# MY_AVR.net
KiCad netlist of a schematic drawn in Altium Designer
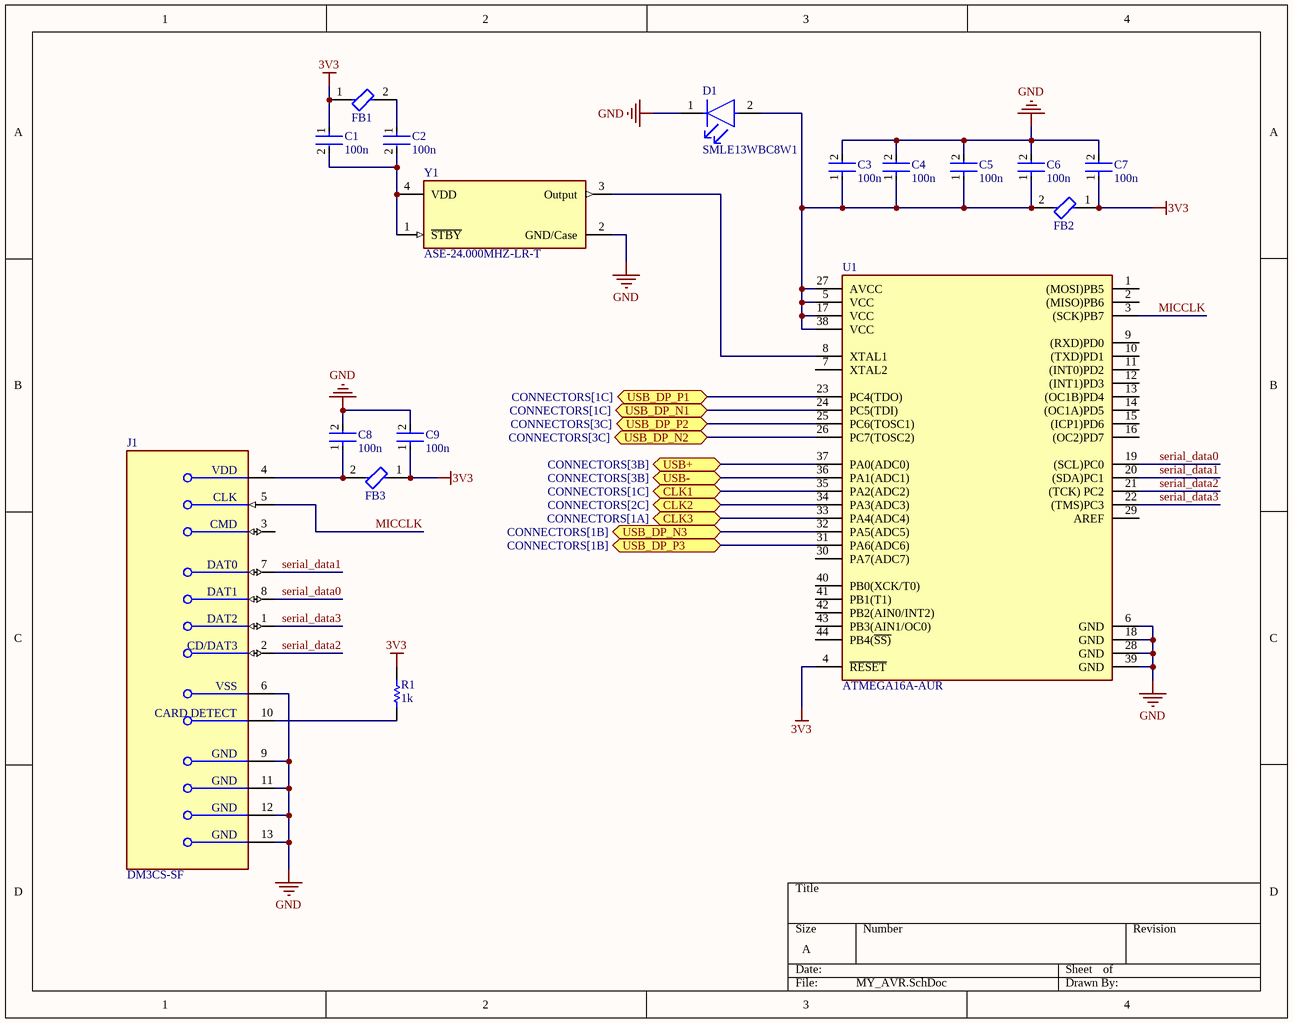
[diagram p0: MY_AVR.SchDoc]

(export (version "E")
  (design (tool "Eeschema 10.0.6"))
  (components
    (comp (ref "C1")
      (value "100n")
      (footprint "FP-CL10-IPC_C")
      (description "Cap Ceramic 4.7uF 10V X5R ±10% Pad SMD 0603 +85°C T/R")
      (fields (field (name "TOLERANCE") "10%"))
      (libsource (lib "Altium Content Vault") (part "b4654b650e69147ec39a6b967a45e02"))
    )
    (comp (ref "C2")
      (value "100n")
      (footprint "FP-CL10-IPC_C")
      (description "Cap Ceramic 4.7uF 10V X5R ±10% Pad SMD 0603 +85°C T/R")
      (fields (field (name "TOLERANCE") "10%"))
      (libsource (lib "Altium Content Vault") (part "b4654b650e69147ec39a6b967a45e02"))
    )
    (comp (ref "C3")
      (value "100n")
      (footprint "FP-CL10-IPC_C")
      (description "Cap Ceramic 4.7uF 10V X5R ±10% Pad SMD 0603 +85°C T/R")
      (fields (field (name "TOLERANCE") "10%"))
      (libsource (lib "Altium Content Vault") (part "b4654b650e69147ec39a6b967a45e02"))
    )
    (comp (ref "C4")
      (value "100n")
      (footprint "FP-CL10-IPC_C")
      (description "Cap Ceramic 4.7uF 10V X5R ±10% Pad SMD 0603 +85°C T/R")
      (fields (field (name "TOLERANCE") "10%"))
      (libsource (lib "Altium Content Vault") (part "b4654b650e69147ec39a6b967a45e02"))
    )
    (comp (ref "C5")
      (value "100n")
      (footprint "FP-CL10-IPC_C")
      (description "Cap Ceramic 4.7uF 10V X5R ±10% Pad SMD 0603 +85°C T/R")
      (fields (field (name "TOLERANCE") "10%"))
      (libsource (lib "Altium Content Vault") (part "b4654b650e69147ec39a6b967a45e02"))
    )
    (comp (ref "C6")
      (value "100n")
      (footprint "FP-CL10-IPC_C")
      (description "Cap Ceramic 4.7uF 10V X5R ±10% Pad SMD 0603 +85°C T/R")
      (fields (field (name "TOLERANCE") "10%"))
      (libsource (lib "Altium Content Vault") (part "b4654b650e69147ec39a6b967a45e02"))
    )
    (comp (ref "C7")
      (value "100n")
      (footprint "FP-CL10-IPC_C")
      (description "Cap Ceramic 4.7uF 10V X5R ±10% Pad SMD 0603 +85°C T/R")
      (fields (field (name "TOLERANCE") "10%"))
      (libsource (lib "Altium Content Vault") (part "b4654b650e69147ec39a6b967a45e02"))
    )
    (comp (ref "C8")
      (value "100n")
      (footprint "FP-CL10-IPC_C")
      (description "Cap Ceramic 4.7uF 10V X5R ±10% Pad SMD 0603 +85°C T/R")
      (fields (field (name "TOLERANCE") "10%"))
      (libsource (lib "Altium Content Vault") (part "b4654b650e69147ec39a6b967a45e02"))
    )
    (comp (ref "C9")
      (value "100n")
      (footprint "FP-CL10-IPC_C")
      (description "Cap Ceramic 4.7uF 10V X5R ±10% Pad SMD 0603 +85°C T/R")
      (fields (field (name "TOLERANCE") "10%"))
      (libsource (lib "Altium Content Vault") (part "b4654b650e69147ec39a6b967a45e02"))
    )
    (comp (ref "D1")
      (value "SMLE13WBC8W1")
      (footprint "FP-SMLE13WBC8W1-MFG")
      (description "LED WHITE 0603 SMD")
      (fields
        (field (name "OCTOPART") "https://octopart.com/smle13wbc8w1-rohm-22224565")
        (field (name "MANUFACTURER") "Rohm")
      )
      (libsource (lib "Altium Content Vault") (part "8706943c75ba83719d021d2fdc84c58"))
    )
    (comp (ref "FB1")
      (value "BLM18KG121TN1D")
      (footprint "FP-BLM18-0_15-t0_6-d1_2-IPC_A")
      (description "FERRITE BEAD 120 OHM 0603 1LN")
      (fields (field (name "TOLERANCE") "25%"))
      (libsource (lib "Altium Content Vault") (part "5f30dd21d616792df468990f7003faa"))
    )
    (comp (ref "FB2")
      (value "BLM18KG121TN1D")
      (footprint "FP-BLM18-0_15-t0_6-d1_2-IPC_A")
      (description "FERRITE BEAD 120 OHM 0603 1LN")
      (fields (field (name "TOLERANCE") "25%"))
      (libsource (lib "Altium Content Vault") (part "5f30dd21d616792df468990f7003faa"))
    )
    (comp (ref "FB3")
      (value "BLM18KG121TN1D")
      (footprint "FP-BLM18-0_15-t0_6-d1_2-IPC_A")
      (description "FERRITE BEAD 120 OHM 0603 1LN")
      (fields (field (name "TOLERANCE") "25%"))
      (libsource (lib "Altium Content Vault") (part "5f30dd21d616792df468990f7003faa"))
    )
    (comp (ref "J1")
      (value "DM3CS-SF")
      (footprint "FP-DM3CS-SF-MFG")
      (description "CONN MICRO SD CARD HINGED TYPE")
      (libsource (lib "Altium Content Vault") (part "bac915de5305cfdd1ca301aae530106"))
    )
    (comp (ref "R1")
      (value "1k")
      (footprint "RESC2013X60X35ML10T20")
      (fields (field (name "TOLERANCE") "5%") (field (name "MANUFACTURER") "Yageo"))
      (libsource (lib "Altium Content Vault") (part "RES-2"))
    )
    (comp (ref "U1")
      (value "ATMEGA16A-AUR")
      (footprint "FP-44A-MFG")
      (description "IC MCU 8BIT 16KB FLASH 44TQFP")
      (libsource (lib "Altium Content Vault") (part "ed42ffdc3273df72733ccc2dd2ee123"))
    )
    (comp (ref "Y1")
      (value "ASE-24.000MHZ-LR-T")
      (footprint "FP-ASE-MFG")
      (description "XTAL Oscillator 24MHz ±25ppm CMOS 3.3V 4-SMD 3.2mm x 2.5mm")
      (libsource (lib "Altium Content Vault") (part "61a724e6190563596ac712fef61ad37"))
    )
  )
  (nets
    (net (code "1") (name "/CLK1") (class "Default")
      (node (ref "U1") (pin "35") (pinfunction "PA2(ADC2)_35") (pintype "passive"))
    )
    (net (code "2") (name "/CLK2") (class "Default")
      (node (ref "U1") (pin "34") (pinfunction "PA3(ADC3)_34") (pintype "passive"))
    )
    (net (code "3") (name "/CLK3") (class "Default")
      (node (ref "U1") (pin "33") (pinfunction "PA4(ADC4)_33") (pintype "passive"))
    )
    (net (code "4") (name "/MICCLK") (class "Default")
      (node (ref "J1") (pin "5") (pinfunction "CLK_5") (pintype "input"))
      (node (ref "U1") (pin "3") (pinfunction "(SCK)PB7_3") (pintype "passive"))
    )
    (net (code "5") (name "/USB+") (class "Default")
      (node (ref "U1") (pin "37") (pinfunction "PA0(ADC0)_37") (pintype "passive"))
    )
    (net (code "6") (name "/USB-") (class "Default")
      (node (ref "U1") (pin "36") (pinfunction "PA1(ADC1)_36") (pintype "passive"))
    )
    (net (code "7") (name "/USB_DP_N1") (class "Default")
      (node (ref "U1") (pin "24") (pinfunction "PC5(TDI)_24") (pintype "passive"))
    )
    (net (code "8") (name "/USB_DP_N2") (class "Default")
      (node (ref "U1") (pin "26") (pinfunction "PC7(TOSC2)_26") (pintype "passive"))
    )
    (net (code "9") (name "/USB_DP_N3") (class "Default")
      (node (ref "U1") (pin "32") (pinfunction "PA5(ADC5)_32") (pintype "passive"))
    )
    (net (code "10") (name "/USB_DP_P1") (class "Default")
      (node (ref "U1") (pin "23") (pinfunction "PC4(TDO)_23") (pintype "passive"))
    )
    (net (code "11") (name "/USB_DP_P2") (class "Default")
      (node (ref "U1") (pin "25") (pinfunction "PC6(TOSC1)_25") (pintype "passive"))
    )
    (net (code "12") (name "/USB_DP_P3") (class "Default")
      (node (ref "U1") (pin "31") (pinfunction "PA6(ADC6)_31") (pintype "passive"))
    )
    (net (code "13") (name "/serial_data0") (class "Default")
      (node (ref "J1") (pin "8") (pinfunction "DAT1_8") (pintype "bidirectional"))
      (node (ref "U1") (pin "19") (pinfunction "(SCL)PC0_19") (pintype "passive"))
    )
    (net (code "14") (name "/serial_data1") (class "Default")
      (node (ref "J1") (pin "7") (pinfunction "DAT0_7") (pintype "bidirectional"))
      (node (ref "U1") (pin "20") (pinfunction "(SDA)PC1_20") (pintype "passive"))
    )
    (net (code "15") (name "/serial_data2") (class "Default")
      (node (ref "J1") (pin "2") (pinfunction "CD/DAT3_2") (pintype "bidirectional"))
      (node (ref "U1") (pin "21") (pinfunction "(TCK)_PC2_21") (pintype "passive"))
    )
    (net (code "16") (name "/serial_data3") (class "Default")
      (node (ref "J1") (pin "1") (pinfunction "DAT2_1") (pintype "bidirectional"))
      (node (ref "U1") (pin "22") (pinfunction "(TMS)PC3_22") (pintype "passive"))
    )
    (net (code "17") (name "3V3") (class "Default")
      (node (ref "C1") (pin "1") (pinfunction "1_1") (pintype "passive"))
      (node (ref "C7") (pin "1") (pinfunction "1_1") (pintype "passive"))
      (node (ref "C9") (pin "1") (pinfunction "1_1") (pintype "passive"))
      (node (ref "FB1") (pin "1") (pinfunction "1_1") (pintype "passive"))
      (node (ref "FB2") (pin "1") (pinfunction "1_1") (pintype "passive"))
      (node (ref "FB3") (pin "1") (pinfunction "1_1") (pintype "passive"))
      (node (ref "R1") (pin "1") (pinfunction "1_1") (pintype "passive"))
      (node (ref "U1") (pin "4") (pinfunction "~{RESET}_4") (pintype "passive"))
    )
    (net (code "18") (name "GND") (class "Default")
      (node (ref "C3") (pin "2") (pinfunction "2_2") (pintype "passive"))
      (node (ref "C4") (pin "2") (pinfunction "2_2") (pintype "passive"))
      (node (ref "C5") (pin "2") (pinfunction "2_2") (pintype "passive"))
      (node (ref "C6") (pin "2") (pinfunction "2_2") (pintype "passive"))
      (node (ref "C7") (pin "2") (pinfunction "2_2") (pintype "passive"))
      (node (ref "C8") (pin "2") (pinfunction "2_2") (pintype "passive"))
      (node (ref "C9") (pin "2") (pinfunction "2_2") (pintype "passive"))
      (node (ref "D1") (pin "1") (pinfunction "C_1") (pintype "passive"))
      (node (ref "J1") (pin "11") (pinfunction "GND_11") (pintype "power_in"))
      (node (ref "J1") (pin "12") (pinfunction "GND_12") (pintype "power_in"))
      (node (ref "J1") (pin "13") (pinfunction "GND_13") (pintype "power_in"))
      (node (ref "J1") (pin "6") (pinfunction "VSS_6") (pintype "power_in"))
      (node (ref "J1") (pin "9") (pinfunction "GND_9") (pintype "power_in"))
      (node (ref "U1") (pin "18") (pinfunction "GND_18") (pintype "passive"))
      (node (ref "U1") (pin "28") (pinfunction "GND_28") (pintype "passive"))
      (node (ref "U1") (pin "39") (pinfunction "GND_39") (pintype "passive"))
      (node (ref "U1") (pin "6") (pinfunction "GND_6") (pintype "passive"))
      (node (ref "Y1") (pin "2") (pinfunction "GND/Case_2") (pintype "power_in"))
    )
    (net (code "19") (name "Net-(C2-Pad1)") (class "Default")
      (node (ref "C2") (pin "1") (pinfunction "1_1") (pintype "passive"))
      (node (ref "FB1") (pin "2") (pinfunction "2_2") (pintype "passive"))
    )
    (net (code "20") (name "Net-(D1-A)") (class "Default")
      (node (ref "C3") (pin "1") (pinfunction "1_1") (pintype "passive"))
      (node (ref "C4") (pin "1") (pinfunction "1_1") (pintype "passive"))
      (node (ref "C5") (pin "1") (pinfunction "1_1") (pintype "passive"))
      (node (ref "C6") (pin "1") (pinfunction "1_1") (pintype "passive"))
      (node (ref "D1") (pin "2") (pinfunction "A_2") (pintype "passive"))
      (node (ref "FB2") (pin "2") (pinfunction "2_2") (pintype "passive"))
      (node (ref "U1") (pin "17") (pinfunction "VCC_17") (pintype "passive"))
      (node (ref "U1") (pin "27") (pinfunction "AVCC_27") (pintype "passive"))
      (node (ref "U1") (pin "38") (pinfunction "VCC_38") (pintype "passive"))
      (node (ref "U1") (pin "5") (pinfunction "VCC_5") (pintype "passive"))
    )
    (net (code "21") (name "Net-(J1-CARD_DETECT)") (class "Default")
      (node (ref "J1") (pin "10") (pinfunction "CARD_DETECT_10") (pintype "passive"))
      (node (ref "R1") (pin "2") (pinfunction "2_2") (pintype "passive"))
    )
    (net (code "22") (name "Net-(J1-VDD)") (class "Default")
      (node (ref "C8") (pin "1") (pinfunction "1_1") (pintype "passive"))
      (node (ref "FB3") (pin "2") (pinfunction "2_2") (pintype "passive"))
      (node (ref "J1") (pin "4") (pinfunction "VDD_4") (pintype "power_in"))
    )
    (net (code "23") (name "Net-(U1-XTAL1)") (class "Default")
      (node (ref "U1") (pin "8") (pinfunction "XTAL1_8") (pintype "passive"))
      (node (ref "Y1") (pin "3") (pinfunction "Output_3") (pintype "output"))
    )
    (net (code "24") (name "Net-(Y1-VDD)") (class "Default")
      (node (ref "C1") (pin "2") (pinfunction "2_2") (pintype "passive"))
      (node (ref "C2") (pin "2") (pinfunction "2_2") (pintype "passive"))
      (node (ref "Y1") (pin "1") (pinfunction "~{STBY}_1") (pintype "input"))
      (node (ref "Y1") (pin "4") (pinfunction "VDD_4") (pintype "power_in"))
    )
    (net (code "25") (name "unconnected-(J1-CMD-Pad3)") (class "Default")
      (node (ref "J1") (pin "3") (pinfunction "CMD_3") (pintype "bidirectional"))
    )
    (net (code "26") (name "unconnected-(U1-(ICP1)PD6-Pad15)") (class "Default")
      (node (ref "U1") (pin "15") (pinfunction "(ICP1)PD6_15") (pintype "passive"))
    )
    (net (code "27") (name "unconnected-(U1-(INT0)PD2-Pad11)") (class "Default")
      (node (ref "U1") (pin "11") (pinfunction "(INT0)PD2_11") (pintype "passive"))
    )
    (net (code "28") (name "unconnected-(U1-(INT1)PD3-Pad12)") (class "Default")
      (node (ref "U1") (pin "12") (pinfunction "(INT1)PD3_12") (pintype "passive"))
    )
    (net (code "29") (name "unconnected-(U1-(MISO)PB6-Pad2)") (class "Default")
      (node (ref "U1") (pin "2") (pinfunction "(MISO)PB6_2") (pintype "passive"))
    )
    (net (code "30") (name "unconnected-(U1-(MOSI)PB5-Pad1)") (class "Default")
      (node (ref "U1") (pin "1") (pinfunction "(MOSI)PB5_1") (pintype "passive"))
    )
    (net (code "31") (name "unconnected-(U1-(OC1A)PD5-Pad14)") (class "Default")
      (node (ref "U1") (pin "14") (pinfunction "(OC1A)PD5_14") (pintype "passive"))
    )
    (net (code "32") (name "unconnected-(U1-(OC1B)PD4-Pad13)") (class "Default")
      (node (ref "U1") (pin "13") (pinfunction "(OC1B)PD4_13") (pintype "passive"))
    )
    (net (code "33") (name "unconnected-(U1-(OC2)PD7-Pad16)") (class "Default")
      (node (ref "U1") (pin "16") (pinfunction "(OC2)PD7_16") (pintype "passive"))
    )
    (net (code "34") (name "unconnected-(U1-(RXD)PD0-Pad9)") (class "Default")
      (node (ref "U1") (pin "9") (pinfunction "(RXD)PD0_9") (pintype "passive"))
    )
    (net (code "35") (name "unconnected-(U1-(TXD)PD1-Pad10)") (class "Default")
      (node (ref "U1") (pin "10") (pinfunction "(TXD)PD1_10") (pintype "passive"))
    )
    (net (code "36") (name "unconnected-(U1-AREF-Pad29)") (class "Default")
      (node (ref "U1") (pin "29") (pinfunction "AREF_29") (pintype "passive"))
    )
    (net (code "37") (name "unconnected-(U1-PA7(ADC7)-Pad30)") (class "Default")
      (node (ref "U1") (pin "30") (pinfunction "PA7(ADC7)_30") (pintype "passive"))
    )
    (net (code "38") (name "unconnected-(U1-PB0(XCK{slash}T0)-Pad40)") (class "Default")
      (node (ref "U1") (pin "40") (pinfunction "PB0(XCK/T0)_40") (pintype "passive"))
    )
    (net (code "39") (name "unconnected-(U1-PB1(T1)-Pad41)") (class "Default")
      (node (ref "U1") (pin "41") (pinfunction "PB1(T1)_41") (pintype "passive"))
    )
    (net (code "40") (name "unconnected-(U1-PB2(AIN0{slash}INT2)-Pad42)") (class "Default")
      (node (ref "U1") (pin "42") (pinfunction "PB2(AIN0/INT2)_42") (pintype "passive"))
    )
    (net (code "41") (name "unconnected-(U1-PB3(AIN1{slash}OC0)-Pad43)") (class "Default")
      (node (ref "U1") (pin "43") (pinfunction "PB3(AIN1/OC0)_43") (pintype "passive"))
    )
    (net (code "42") (name "unconnected-(U1-PB4(~{SS)}-Pad44)") (class "Default")
      (node (ref "U1") (pin "44") (pinfunction "PB4(~{SS)}_44") (pintype "passive"))
    )
    (net (code "43") (name "unconnected-(U1-XTAL2-Pad7)") (class "Default")
      (node (ref "U1") (pin "7") (pinfunction "XTAL2_7") (pintype "passive"))
    )
  )
)
